# Fascia_physioBoardV0_1.net
KiCad netlist of a schematic drawn in EAGLE
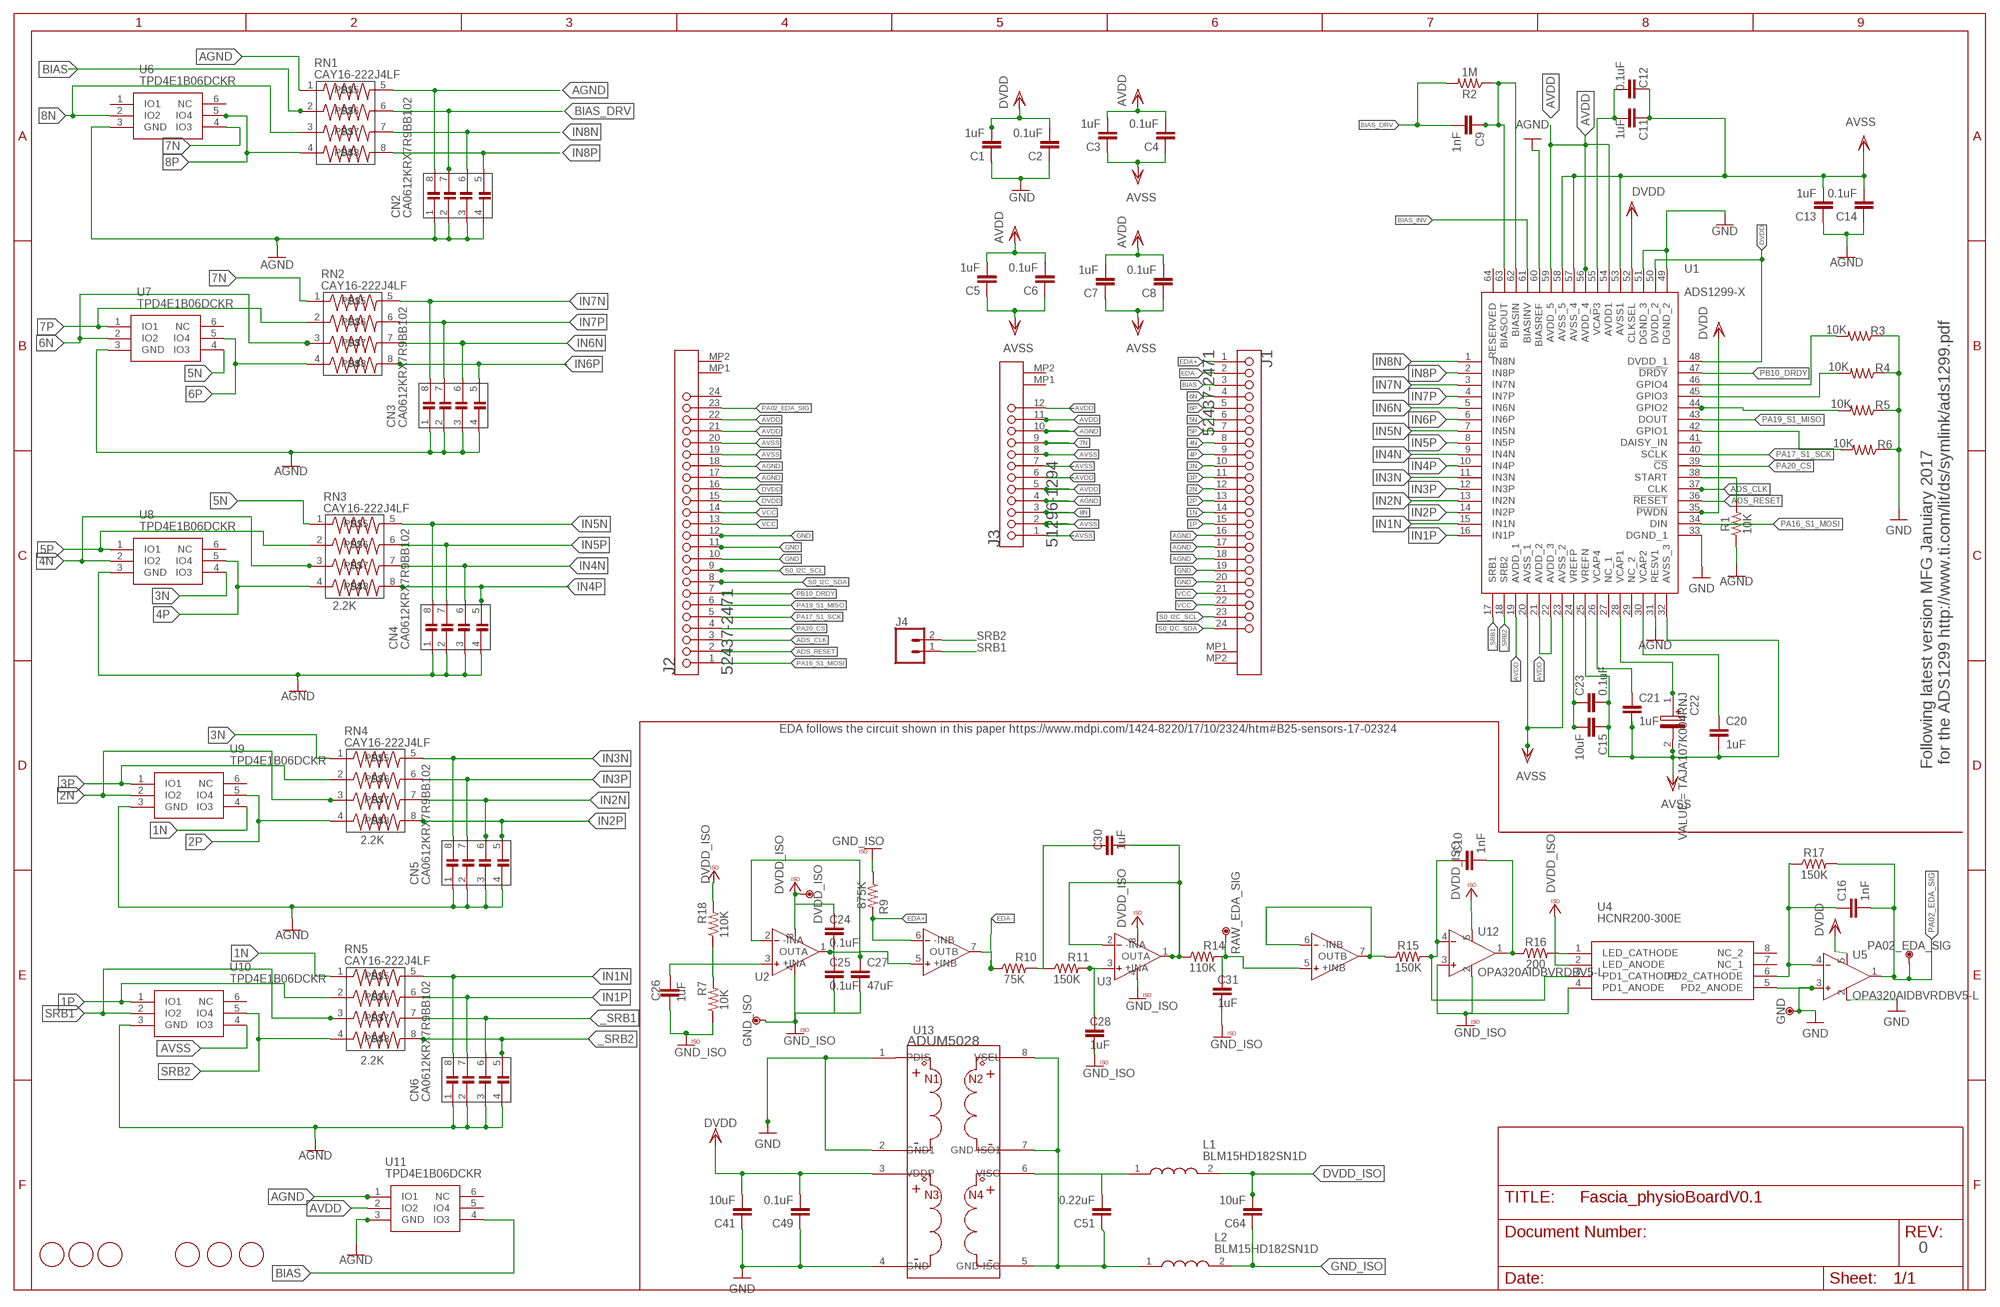
[diagram p0: schematic, sheet 1]

(export (version "E")
  (design (tool "Eeschema 10.0.6"))
  (components
    (comp (ref "C1")
      (value "1uF")
      (footprint "eagle-import:0402-TIGHT")
      (libsource (lib "eagle-import") (part "1UF-0402T-16V-10%"))
    )
    (comp (ref "C2")
      (value "0.1uF")
      (footprint "eagle-import:0402-TIGHT")
      (libsource (lib "eagle-import") (part "0.1UF-0402T-16V-10%"))
    )
    (comp (ref "C3")
      (value "1uF")
      (footprint "eagle-import:0402-TIGHT")
      (libsource (lib "eagle-import") (part "1UF-0402T-16V-10%"))
    )
    (comp (ref "C4")
      (value "0.1uF")
      (footprint "eagle-import:0402-TIGHT")
      (libsource (lib "eagle-import") (part "0.1UF-0402T-16V-10%"))
    )
    (comp (ref "C5")
      (value "1uF")
      (footprint "eagle-import:0402-TIGHT")
      (libsource (lib "eagle-import") (part "1UF-0402T-16V-10%"))
    )
    (comp (ref "C6")
      (value "0.1uF")
      (footprint "eagle-import:0402-TIGHT")
      (libsource (lib "eagle-import") (part "0.1UF-0402T-16V-10%"))
    )
    (comp (ref "C7")
      (value "1uF")
      (footprint "eagle-import:0402-TIGHT")
      (libsource (lib "eagle-import") (part "1UF-0402T-16V-10%"))
    )
    (comp (ref "C8")
      (value "0.1uF")
      (footprint "eagle-import:0402-TIGHT")
      (libsource (lib "eagle-import") (part "0.1UF-0402T-16V-10%"))
    )
    (comp (ref "C9")
      (value "1nF")
      (footprint "eagle-import:0402-TIGHT")
      (libsource (lib "eagle-import") (part "1NF-0402T-16V-10%"))
    )
    (comp (ref "C10")
      (value "1nF")
      (footprint "eagle-import:0402-TIGHT")
      (libsource (lib "eagle-import") (part "1NF-0402T-16V-10%"))
    )
    (comp (ref "C11")
      (value "1uF")
      (footprint "eagle-import:0402-TIGHT")
      (libsource (lib "eagle-import") (part "1UF-0402T-16V-10%"))
    )
    (comp (ref "C12")
      (value "0.1uF")
      (footprint "eagle-import:0402-TIGHT")
      (libsource (lib "eagle-import") (part "0.1UF-0402T-16V-10%"))
    )
    (comp (ref "C13")
      (value "1uF")
      (footprint "eagle-import:0402-TIGHT")
      (libsource (lib "eagle-import") (part "1UF-0402T-16V-10%"))
    )
    (comp (ref "C14")
      (value "0.1uF")
      (footprint "eagle-import:0402-TIGHT")
      (libsource (lib "eagle-import") (part "0.1UF-0402T-16V-10%"))
    )
    (comp (ref "C15")
      (value "10uF")
      (footprint "eagle-import:0402")
      (libsource (lib "eagle-import") (part "0.1UF-0402-16V-10%"))
    )
    (comp (ref "C16")
      (value "1nF")
      (footprint "eagle-import:0402-TIGHT")
      (libsource (lib "eagle-import") (part "1NF-0402T-16V-10%"))
    )
    (comp (ref "C20")
      (value "1uF")
      (footprint "eagle-import:0402-TIGHT")
      (libsource (lib "eagle-import") (part "1UF-0402T-16V-10%"))
    )
    (comp (ref "C21")
      (value "1uF")
      (footprint "eagle-import:0402-TIGHT")
      (libsource (lib "eagle-import") (part "1UF-0402T-16V-10%"))
    )
    (comp (ref "C22")
      (value "TAJA107K004RNJ")
      (footprint "eagle-import:CAPPM3216X180N")
      (fields
        (field (name "MOUSER_PART_NUMBER") "581-TAJA107K004RNJ")
        (field (name "RS_PART_NUMBER") "1360130")
      )
      (libsource (lib "eagle-import") (part "TAJA107K004RNJ"))
    )
    (comp (ref "C23")
      (value "0.1uF")
      (footprint "eagle-import:0402-TIGHT")
      (libsource (lib "eagle-import") (part "0.1UF-0402T-16V-10%"))
    )
    (comp (ref "C24")
      (value "0.1uF")
      (footprint "eagle-import:0402-TIGHT")
      (libsource (lib "eagle-import") (part "0.1UF-0402T-16V-10%"))
    )
    (comp (ref "C25")
      (value "0.1uF")
      (footprint "eagle-import:0402-TIGHT")
      (libsource (lib "eagle-import") (part "0.1UF-0402T-16V-10%"))
    )
    (comp (ref "C26")
      (value "1uF")
      (footprint "eagle-import:0402-TIGHT")
      (libsource (lib "eagle-import") (part "1UF-0402T-16V-10%"))
    )
    (comp (ref "C27")
      (value "47uF")
      (footprint "eagle-import:0603")
      (libsource (lib "eagle-import") (part "47UF-0603-25V-5%"))
    )
    (comp (ref "C28")
      (value "1uF")
      (footprint "eagle-import:0402-TIGHT")
      (libsource (lib "eagle-import") (part "1UF-0402T-16V-10%"))
    )
    (comp (ref "C30")
      (value "1uF")
      (footprint "eagle-import:0402-TIGHT")
      (libsource (lib "eagle-import") (part "1UF-0402T-16V-10%"))
    )
    (comp (ref "C31")
      (value "1uF")
      (footprint "eagle-import:0402-TIGHT")
      (libsource (lib "eagle-import") (part "1UF-0402T-16V-10%"))
    )
    (comp (ref "C41")
      (value "10uF")
      (footprint "eagle-import:0603")
      (libsource (lib "eagle-import") (part "10UF-0603-6.3V-20%"))
    )
    (comp (ref "C49")
      (value "0.1uF")
      (footprint "eagle-import:0402-TIGHT")
      (libsource (lib "eagle-import") (part "0.1UF-0402T-16V-10%"))
    )
    (comp (ref "C51")
      (value "0.22uF")
      (footprint "eagle-import:0402-TIGHT")
      (libsource (lib "eagle-import") (part "0.22UF-0402T-16V-10%"))
    )
    (comp (ref "C64")
      (value "10uF")
      (footprint "eagle-import:0603")
      (libsource (lib "eagle-import") (part "10UF-0603-6.3V-20%"))
    )
    (comp (ref "CN2")
      (value "CA0612KRX7R9BB102")
      (footprint "eagle-import:CA0612KRX7R9BB102")
      (fields
        (field (name "MOUSER_PART_NUMBER") "603-CA612KRX7R9BB102")
        (field (name "RS_PART_NUMBER") "6169789")
      )
      (libsource (lib "eagle-import") (part "CA0612KRX7R9BB102"))
    )
    (comp (ref "CN3")
      (value "CA0612KRX7R9BB102")
      (footprint "eagle-import:CA0612KRX7R9BB102")
      (fields
        (field (name "MOUSER_PART_NUMBER") "603-CA612KRX7R9BB102")
        (field (name "RS_PART_NUMBER") "6169789")
      )
      (libsource (lib "eagle-import") (part "CA0612KRX7R9BB102"))
    )
    (comp (ref "CN4")
      (value "CA0612KRX7R9BB102")
      (footprint "eagle-import:CA0612KRX7R9BB102")
      (fields
        (field (name "MOUSER_PART_NUMBER") "603-CA612KRX7R9BB102")
        (field (name "RS_PART_NUMBER") "6169789")
      )
      (libsource (lib "eagle-import") (part "CA0612KRX7R9BB102"))
    )
    (comp (ref "CN5")
      (value "CA0612KRX7R9BB102")
      (footprint "eagle-import:CA0612KRX7R9BB102")
      (fields
        (field (name "MOUSER_PART_NUMBER") "603-CA612KRX7R9BB102")
        (field (name "RS_PART_NUMBER") "6169789")
      )
      (libsource (lib "eagle-import") (part "CA0612KRX7R9BB102"))
    )
    (comp (ref "CN6")
      (value "CA0612KRX7R9BB102")
      (footprint "eagle-import:CA0612KRX7R9BB102")
      (fields
        (field (name "MOUSER_PART_NUMBER") "603-CA612KRX7R9BB102")
        (field (name "RS_PART_NUMBER") "6169789")
      )
      (libsource (lib "eagle-import") (part "CA0612KRX7R9BB102"))
    )
    (comp (ref "DVDD_ISO")
      (value "DNP")
      (footprint "eagle-import:TP-0.8MM")
      (libsource (lib "eagle-import") (part "TPTP-0.8MM"))
    )
    (comp (ref "FD1")
      (value "DNP")
      (footprint "eagle-import:FD-1-1.5")
      (libsource (lib "eagle-import") (part "FIDUCIAL-1.5MM"))
    )
    (comp (ref "FD2")
      (value "DNP")
      (footprint "eagle-import:FD-1-1.5")
      (libsource (lib "eagle-import") (part "FIDUCIAL-1.5MM"))
    )
    (comp (ref "FD3")
      (value "DNP")
      (footprint "eagle-import:FD-1-1.5")
      (libsource (lib "eagle-import") (part "FIDUCIAL-1.5MM"))
    )
    (comp (ref "FD4")
      (value "DNP")
      (footprint "eagle-import:FD-1-1.5")
      (libsource (lib "eagle-import") (part "FIDUCIAL-1.5MM"))
    )
    (comp (ref "FD5")
      (value "DNP")
      (footprint "eagle-import:FD-1-1.5")
      (libsource (lib "eagle-import") (part "FIDUCIAL-1.5MM"))
    )
    (comp (ref "FD6")
      (value "DNP")
      (footprint "eagle-import:FD-1-1.5")
      (libsource (lib "eagle-import") (part "FIDUCIAL-1.5MM"))
    )
    (comp (ref "GND")
      (value "DNP")
      (footprint "eagle-import:TP-0.8MM")
      (libsource (lib "eagle-import") (part "TPTP-0.8MM"))
    )
    (comp (ref "GND_ISO")
      (value "DNP")
      (footprint "eagle-import:TP-0.8MM")
      (libsource (lib "eagle-import") (part "TPTP-0.8MM"))
    )
    (comp (ref "J1")
      (value "MOLEX_52437-2471MOLEX_52437-2471_0_0")
      (footprint "eagle-import:MOLEX_52437-2471_0")
      (fields (field (name "MF") "Molex") (field (name "MPN") "52437-2471"))
      (libsource (lib "eagle-import") (part "MOLEX_52437-2471MOLEX_52437-2471_0_0"))
    )
    (comp (ref "J2")
      (value "MOLEX_52437-2471MOLEX_52437-2471_0_0")
      (footprint "eagle-import:MOLEX_52437-2471_0")
      (fields (field (name "MF") "Molex") (field (name "MPN") "52437-2471"))
      (libsource (lib "eagle-import") (part "MOLEX_52437-2471MOLEX_52437-2471_0_0"))
    )
    (comp (ref "J3")
      (value "MOLEX_51296-1294MOLEX_51296-1294_0_0")
      (footprint "eagle-import:MOLEX_51296-1294_0")
      (fields (field (name "MF") "Molex") (field (name "MPN") "51296-1294"))
      (libsource (lib "eagle-import") (part "MOLEX_51296-1294MOLEX_51296-1294_0_0"))
    )
    (comp (ref "J4")
      (value "CONN_02")
      (footprint "eagle-import:1X02")
      (libsource (lib "eagle-import") (part "CONN_02"))
    )
    (comp (ref "L1")
      (value "BLM15HD182SN1D")
      (footprint "eagle-import:INDC1005X55N")
      (fields
        (field (name "MOUSER_PART_NUMBER") "81-BLM15HD182SN1D")
        (field (name "RS_PART_NUMBER") "7926224P")
      )
      (libsource (lib "eagle-import") (part "BLM15HD182SN1D"))
    )
    (comp (ref "L2")
      (value "BLM15HD182SN1D")
      (footprint "eagle-import:INDC1005X55N")
      (fields
        (field (name "MOUSER_PART_NUMBER") "81-BLM15HD182SN1D")
        (field (name "RS_PART_NUMBER") "7926224P")
      )
      (libsource (lib "eagle-import") (part "BLM15HD182SN1D"))
    )
    (comp (ref "PA02_EDA_SIG")
      (value "DNP")
      (footprint "eagle-import:TP-0.8MM")
      (libsource (lib "eagle-import") (part "TPTP-0.8MM"))
    )
    (comp (ref "R1")
      (value "10K")
      (footprint "eagle-import:0402-TIGHT")
      (libsource (lib "eagle-import") (part "10K"))
    )
    (comp (ref "R2")
      (value "1M")
      (footprint "eagle-import:0402-TIGHT")
      (libsource (lib "eagle-import") (part "1M"))
    )
    (comp (ref "R3")
      (value "10K")
      (footprint "eagle-import:0402-TIGHT")
      (libsource (lib "eagle-import") (part "10K"))
    )
    (comp (ref "R4")
      (value "10K")
      (footprint "eagle-import:0402-TIGHT")
      (libsource (lib "eagle-import") (part "10K"))
    )
    (comp (ref "R5")
      (value "10K")
      (footprint "eagle-import:0402-TIGHT")
      (libsource (lib "eagle-import") (part "10K"))
    )
    (comp (ref "R6")
      (value "10K")
      (footprint "eagle-import:0402-TIGHT")
      (libsource (lib "eagle-import") (part "10K"))
    )
    (comp (ref "R7")
      (value "10K")
      (footprint "eagle-import:0402-TIGHT")
      (libsource (lib "eagle-import") (part "10K"))
    )
    (comp (ref "R9")
      (value "875K")
      (footprint "eagle-import:0402-TIGHT")
      (libsource (lib "eagle-import") (part "875K"))
    )
    (comp (ref "R10")
      (value "75K")
      (footprint "eagle-import:0402-TIGHT")
      (libsource (lib "eagle-import") (part "75K"))
    )
    (comp (ref "R11")
      (value "150K")
      (footprint "eagle-import:0402-TIGHT")
      (libsource (lib "eagle-import") (part "150K"))
    )
    (comp (ref "R14")
      (value "110K")
      (footprint "eagle-import:0402-TIGHT")
      (libsource (lib "eagle-import") (part "110K"))
    )
    (comp (ref "R15")
      (value "150K")
      (footprint "eagle-import:0402-TIGHT")
      (libsource (lib "eagle-import") (part "150K"))
    )
    (comp (ref "R16")
      (value "200")
      (footprint "eagle-import:0402-TIGHT")
      (libsource (lib "eagle-import") (part "200"))
    )
    (comp (ref "R17")
      (value "150K")
      (footprint "eagle-import:0402-TIGHT")
      (libsource (lib "eagle-import") (part "150K"))
    )
    (comp (ref "R18")
      (value "110K")
      (footprint "eagle-import:0402-TIGHT")
      (libsource (lib "eagle-import") (part "110K"))
    )
    (comp (ref "RAW_EDA_SIG")
      (value "DNP")
      (footprint "eagle-import:TP-0.8MM")
      (libsource (lib "eagle-import") (part "TPTP-0.8MM"))
    )
    (comp (ref "RN1")
      (value "CAY16-222J4LF")
      (footprint "eagle-import:CAY16-222J4LF")
      (fields (field (name "MANUFACTURER_PART_NUMBER") "CAY16-222J4LF  "))
      (libsource (lib "eagle-import") (part "CAY16-222J4LF"))
    )
    (comp (ref "RN2")
      (value "CAY16-222J4LF")
      (footprint "eagle-import:CAY16-222J4LF")
      (fields (field (name "MANUFACTURER_PART_NUMBER") "CAY16-222J4LF  "))
      (libsource (lib "eagle-import") (part "CAY16-222J4LF"))
    )
    (comp (ref "RN3")
      (value "CAY16-222J4LF")
      (footprint "eagle-import:CAY16-222J4LF")
      (fields (field (name "MANUFACTURER_PART_NUMBER") "CAY16-222J4LF  "))
      (libsource (lib "eagle-import") (part "CAY16-222J4LF"))
    )
    (comp (ref "RN4")
      (value "CAY16-222J4LF")
      (footprint "eagle-import:CAY16-222J4LF")
      (fields (field (name "MANUFACTURER_PART_NUMBER") "CAY16-222J4LF  "))
      (libsource (lib "eagle-import") (part "CAY16-222J4LF"))
    )
    (comp (ref "RN5")
      (value "CAY16-222J4LF")
      (footprint "eagle-import:CAY16-222J4LF")
      (fields (field (name "MANUFACTURER_PART_NUMBER") "CAY16-222J4LF  "))
      (libsource (lib "eagle-import") (part "CAY16-222J4LF"))
    )
    (comp (ref "U1")
      (value "ADS1299-X")
      (footprint "eagle-import:QFP50P1200X1200X120-64N")
      (libsource (lib "eagle-import") (part "ADS1299-X"))
    )
    (comp (ref "U2")
      (value "OPA2320AIDGKT_NOVA8-SOIC-L")
      (footprint "eagle-import:D8-L")
      (libsource (lib "eagle-import") (part "OPA2320AIDGKT_NOVA8-SOIC-L"))
    )
    (comp (ref "U3")
      (value "OPA2320AIDGKT_NOVAL8-SOIC-L")
      (footprint "eagle-import:D8-L")
      (libsource (lib "eagle-import") (part "OPA2320AIDGKT_NOVAL8-SOIC-L"))
    )
    (comp (ref "U4")
      (value "HCNR200-300E")
      (footprint "eagle-import:SOP254P1230X400-8N")
      (fields
        (field (name "MOUSER_PART_NUMBER") "630-HCNR200-300E")
        (field (name "RS_PART_NUMBER") "6935264P")
      )
      (libsource (lib "eagle-import") (part "HCNR200-300E"))
    )
    (comp (ref "U5")
      (value "OPA320AIDBVRDBV5-L")
      (footprint "eagle-import:DBV5-L")
      (fields (field (name "MANUFACTURER_PART_NUMBER") "OPA320AIDBVR"))
      (libsource (lib "eagle-import") (part "OPA320AIDBVRDBV5-L"))
    )
    (comp (ref "U6")
      (value "TPD4E1B06DCKR")
      (footprint "eagle-import:SOT65P210X110-6N")
      (fields
        (field (name "MOUSER_PART_NUMBER") "595-TPD4E1B06DCKR")
        (field (name "RS_PART_NUMBER") "8255330P")
      )
      (libsource (lib "eagle-import") (part "TPD4E1B06DCKR"))
    )
    (comp (ref "U7")
      (value "TPD4E1B06DCKR")
      (footprint "eagle-import:SOT65P210X110-6N")
      (fields
        (field (name "MOUSER_PART_NUMBER") "595-TPD4E1B06DCKR")
        (field (name "RS_PART_NUMBER") "8255330P")
      )
      (libsource (lib "eagle-import") (part "TPD4E1B06DCKR"))
    )
    (comp (ref "U8")
      (value "TPD4E1B06DCKR")
      (footprint "eagle-import:SOT65P210X110-6N")
      (fields
        (field (name "MOUSER_PART_NUMBER") "595-TPD4E1B06DCKR")
        (field (name "RS_PART_NUMBER") "8255330P")
      )
      (libsource (lib "eagle-import") (part "TPD4E1B06DCKR"))
    )
    (comp (ref "U9")
      (value "TPD4E1B06DCKR")
      (footprint "eagle-import:SOT65P210X110-6N")
      (fields
        (field (name "MOUSER_PART_NUMBER") "595-TPD4E1B06DCKR")
        (field (name "RS_PART_NUMBER") "8255330P")
      )
      (libsource (lib "eagle-import") (part "TPD4E1B06DCKR"))
    )
    (comp (ref "U10")
      (value "TPD4E1B06DCKR")
      (footprint "eagle-import:SOT65P210X110-6N")
      (fields
        (field (name "MOUSER_PART_NUMBER") "595-TPD4E1B06DCKR")
        (field (name "RS_PART_NUMBER") "8255330P")
      )
      (libsource (lib "eagle-import") (part "TPD4E1B06DCKR"))
    )
    (comp (ref "U11")
      (value "TPD4E1B06DCKR")
      (footprint "eagle-import:SOT65P210X110-6N")
      (fields
        (field (name "MOUSER_PART_NUMBER") "595-TPD4E1B06DCKR")
        (field (name "RS_PART_NUMBER") "8255330P")
      )
      (libsource (lib "eagle-import") (part "TPD4E1B06DCKR"))
    )
    (comp (ref "U12")
      (value "OPA320AIDBVRDBV5-L")
      (footprint "eagle-import:DBV5-L")
      (fields (field (name "MANUFACTURER_PART_NUMBER") "OPA320AIDBVR"))
      (libsource (lib "eagle-import") (part "OPA320AIDBVRDBV5-L"))
    )
    (comp (ref "U13")
      (value "ADUM5028")
      (footprint "eagle-import:SOIC_IC")
      (libsource (lib "eagle-import") (part "ADUM5028"))
    )
  )
  (nets
    (net (code "1") (name "/N$12") (class "Default")
      (node (ref "C26") (pin "1") (pinfunction "1_1") (pintype "passive"))
      (node (ref "R18") (pin "1") (pinfunction "1_1") (pintype "passive"))
      (node (ref "R7") (pin "2") (pinfunction "2_2") (pintype "passive"))
      (node (ref "U2") (pin "3") (pinfunction "+INA_3") (pintype "input"))
    )
    (net (code "2") (name "1N") (class "Default")
      (node (ref "J1") (pin "14") (pinfunction "14_14") (pintype "passive"))
      (node (ref "RN5") (pin "1") (pinfunction "P$1_1") (pintype "bidirectional"))
      (node (ref "U9") (pin "4") (pinfunction "IO3_4") (pintype "bidirectional"))
    )
    (net (code "3") (name "1P") (class "Default")
      (node (ref "J1") (pin "15") (pinfunction "15_15") (pintype "passive"))
      (node (ref "RN5") (pin "2") (pinfunction "P$2_2") (pintype "bidirectional"))
      (node (ref "U10") (pin "1") (pinfunction "IO1_1") (pintype "bidirectional"))
    )
    (net (code "4") (name "2N") (class "Default")
      (node (ref "J1") (pin "12") (pinfunction "12_12") (pintype "passive"))
      (node (ref "RN4") (pin "3") (pinfunction "P$3_3") (pintype "bidirectional"))
      (node (ref "U9") (pin "2") (pinfunction "IO2_2") (pintype "bidirectional"))
    )
    (net (code "5") (name "2P") (class "Default")
      (node (ref "J1") (pin "13") (pinfunction "13_13") (pintype "passive"))
      (node (ref "RN4") (pin "4") (pinfunction "P$4_4") (pintype "bidirectional"))
      (node (ref "U9") (pin "5") (pinfunction "IO4_5") (pintype "bidirectional"))
    )
    (net (code "6") (name "3N") (class "Default")
      (node (ref "J1") (pin "10") (pinfunction "10_10") (pintype "passive"))
      (node (ref "RN4") (pin "1") (pinfunction "P$1_1") (pintype "bidirectional"))
      (node (ref "U8") (pin "4") (pinfunction "IO3_4") (pintype "bidirectional"))
    )
    (net (code "7") (name "3P") (class "Default")
      (node (ref "J1") (pin "11") (pinfunction "11_11") (pintype "passive"))
      (node (ref "RN4") (pin "2") (pinfunction "P$2_2") (pintype "bidirectional"))
      (node (ref "U9") (pin "1") (pinfunction "IO1_1") (pintype "bidirectional"))
    )
    (net (code "8") (name "4N") (class "Default")
      (node (ref "J1") (pin "8") (pinfunction "8_8") (pintype "passive"))
      (node (ref "RN3") (pin "3") (pinfunction "P$3_3") (pintype "bidirectional"))
      (node (ref "U8") (pin "2") (pinfunction "IO2_2") (pintype "bidirectional"))
    )
    (net (code "9") (name "4P") (class "Default")
      (node (ref "J1") (pin "9") (pinfunction "9_9") (pintype "passive"))
      (node (ref "RN3") (pin "4") (pinfunction "P$4_4") (pintype "bidirectional"))
      (node (ref "U8") (pin "5") (pinfunction "IO4_5") (pintype "bidirectional"))
    )
    (net (code "10") (name "5N") (class "Default")
      (node (ref "J1") (pin "6") (pinfunction "6_6") (pintype "passive"))
      (node (ref "RN3") (pin "1") (pinfunction "P$1_1") (pintype "bidirectional"))
      (node (ref "U7") (pin "4") (pinfunction "IO3_4") (pintype "bidirectional"))
    )
    (net (code "11") (name "5P") (class "Default")
      (node (ref "J1") (pin "7") (pinfunction "7_7") (pintype "passive"))
      (node (ref "RN3") (pin "2") (pinfunction "P$2_2") (pintype "bidirectional"))
      (node (ref "U8") (pin "1") (pinfunction "IO1_1") (pintype "bidirectional"))
    )
    (net (code "12") (name "6N") (class "Default")
      (node (ref "J1") (pin "4") (pinfunction "4_4") (pintype "passive"))
      (node (ref "RN2") (pin "3") (pinfunction "P$3_3") (pintype "bidirectional"))
      (node (ref "U7") (pin "2") (pinfunction "IO2_2") (pintype "bidirectional"))
    )
    (net (code "13") (name "6P") (class "Default")
      (node (ref "J1") (pin "5") (pinfunction "5_5") (pintype "passive"))
      (node (ref "RN2") (pin "4") (pinfunction "P$4_4") (pintype "bidirectional"))
      (node (ref "U7") (pin "5") (pinfunction "IO4_5") (pintype "bidirectional"))
    )
    (net (code "14") (name "7N") (class "Default")
      (node (ref "J3") (pin "9") (pinfunction "9_9") (pintype "passive"))
      (node (ref "RN2") (pin "1") (pinfunction "P$1_1") (pintype "bidirectional"))
      (node (ref "U6") (pin "4") (pinfunction "IO3_4") (pintype "bidirectional"))
    )
    (net (code "15") (name "7P") (class "Default")
      (node (ref "RN2") (pin "2") (pinfunction "P$2_2") (pintype "bidirectional"))
      (node (ref "U7") (pin "1") (pinfunction "IO1_1") (pintype "bidirectional"))
    )
    (net (code "16") (name "8N") (class "Default")
      (node (ref "J3") (pin "3") (pinfunction "3_3") (pintype "passive"))
      (node (ref "RN1") (pin "3") (pinfunction "P$3_3") (pintype "bidirectional"))
      (node (ref "U6") (pin "2") (pinfunction "IO2_2") (pintype "bidirectional"))
    )
    (net (code "17") (name "8P") (class "Default")
      (node (ref "RN1") (pin "4") (pinfunction "P$4_4") (pintype "bidirectional"))
      (node (ref "U6") (pin "5") (pinfunction "IO4_5") (pintype "bidirectional"))
    )
    (net (code "18") (name "ADS_CLK") (class "Default")
      (node (ref "J2") (pin "3") (pinfunction "3_3") (pintype "passive"))
      (node (ref "U1") (pin "37") (pinfunction "CLK_37") (pintype "bidirectional"))
    )
    (net (code "19") (name "ADS_RESET") (class "Default")
      (node (ref "J2") (pin "2") (pinfunction "2_2") (pintype "passive"))
      (node (ref "U1") (pin "36") (pinfunction "~{RESET}_36") (pintype "bidirectional"))
    )
    (net (code "20") (name "AGND") (class "Default")
      (node (ref "C13") (pin "1") (pinfunction "1_1") (pintype "passive"))
      (node (ref "C14") (pin "1") (pinfunction "1_1") (pintype "passive"))
      (node (ref "CN2") (pin "1") (pinfunction "C10_1") (pintype "bidirectional"))
      (node (ref "CN2") (pin "2") (pinfunction "C11_2") (pintype "bidirectional"))
      (node (ref "CN2") (pin "3") (pinfunction "C12_3") (pintype "bidirectional"))
      (node (ref "CN2") (pin "4") (pinfunction "C13_4") (pintype "bidirectional"))
      (node (ref "CN2") (pin "8") (pinfunction "C17_8") (pintype "bidirectional"))
      (node (ref "CN3") (pin "1") (pinfunction "C10_1") (pintype "bidirectional"))
      (node (ref "CN3") (pin "2") (pinfunction "C11_2") (pintype "bidirectional"))
      (node (ref "CN3") (pin "3") (pinfunction "C12_3") (pintype "bidirectional"))
      (node (ref "CN3") (pin "4") (pinfunction "C13_4") (pintype "bidirectional"))
      (node (ref "CN4") (pin "1") (pinfunction "C10_1") (pintype "bidirectional"))
      (node (ref "CN4") (pin "2") (pinfunction "C11_2") (pintype "bidirectional"))
      (node (ref "CN4") (pin "3") (pinfunction "C12_3") (pintype "bidirectional"))
      (node (ref "CN4") (pin "4") (pinfunction "C13_4") (pintype "bidirectional"))
      (node (ref "CN5") (pin "1") (pinfunction "C10_1") (pintype "bidirectional"))
      (node (ref "CN5") (pin "2") (pinfunction "C11_2") (pintype "bidirectional"))
      (node (ref "CN5") (pin "3") (pinfunction "C12_3") (pintype "bidirectional"))
      (node (ref "CN5") (pin "4") (pinfunction "C13_4") (pintype "bidirectional"))
      (node (ref "CN6") (pin "1") (pinfunction "C10_1") (pintype "bidirectional"))
      (node (ref "CN6") (pin "2") (pinfunction "C11_2") (pintype "bidirectional"))
      (node (ref "CN6") (pin "3") (pinfunction "C12_3") (pintype "bidirectional"))
      (node (ref "CN6") (pin "4") (pinfunction "C13_4") (pintype "bidirectional"))
      (node (ref "J1") (pin "16") (pinfunction "16_16") (pintype "passive"))
      (node (ref "J1") (pin "17") (pinfunction "17_17") (pintype "passive"))
      (node (ref "J1") (pin "18") (pinfunction "18_18") (pintype "passive"))
      (node (ref "J2") (pin "17") (pinfunction "17_17") (pintype "passive"))
      (node (ref "J2") (pin "18") (pinfunction "18_18") (pintype "passive"))
      (node (ref "J3") (pin "10") (pinfunction "10_10") (pintype "passive"))
      (node (ref "J3") (pin "4") (pinfunction "4_4") (pintype "passive"))
      (node (ref "R1") (pin "1") (pinfunction "1_1") (pintype "passive"))
      (node (ref "RN1") (pin "1") (pinfunction "P$1_1") (pintype "bidirectional"))
      (node (ref "RN1") (pin "5") (pinfunction "P$5_5") (pintype "bidirectional"))
      (node (ref "U1") (pin "31") (pinfunction "RESV1_31") (pintype "bidirectional"))
      (node (ref "U1") (pin "60") (pinfunction "BIASREF_60") (pintype "bidirectional"))
      (node (ref "U10") (pin "3") (pinfunction "GND_3") (pintype "power_in"))
      (node (ref "U11") (pin "1") (pinfunction "IO1_1") (pintype "bidirectional"))
      (node (ref "U11") (pin "3") (pinfunction "GND_3") (pintype "power_in"))
      (node (ref "U6") (pin "3") (pinfunction "GND_3") (pintype "power_in"))
      (node (ref "U7") (pin "3") (pinfunction "GND_3") (pintype "power_in"))
      (node (ref "U8") (pin "3") (pinfunction "GND_3") (pintype "power_in"))
      (node (ref "U9") (pin "3") (pinfunction "GND_3") (pintype "power_in"))
    )
    (net (code "21") (name "AVDD") (class "Default")
      (node (ref "C3") (pin "2") (pinfunction "2_2") (pintype "passive"))
      (node (ref "C4") (pin "2") (pinfunction "2_2") (pintype "passive"))
      (node (ref "C5") (pin "2") (pinfunction "2_2") (pintype "passive"))
      (node (ref "C6") (pin "2") (pinfunction "2_2") (pintype "passive"))
      (node (ref "C7") (pin "2") (pinfunction "2_2") (pintype "passive"))
      (node (ref "C8") (pin "2") (pinfunction "2_2") (pintype "passive"))
      (node (ref "J2") (pin "21") (pinfunction "21_21") (pintype "passive"))
      (node (ref "J2") (pin "22") (pinfunction "22_22") (pintype "passive"))
      (node (ref "J3") (pin "11") (pinfunction "11_11") (pintype "passive"))
      (node (ref "J3") (pin "12") (pinfunction "12_12") (pintype "passive"))
      (node (ref "J3") (pin "5") (pinfunction "5_5") (pintype "passive"))
      (node (ref "J3") (pin "6") (pinfunction "6_6") (pintype "passive"))
      (node (ref "U1") (pin "19") (pinfunction "AVDD_1_19") (pintype "bidirectional"))
      (node (ref "U1") (pin "21") (pinfunction "AVDD_2_21") (pintype "bidirectional"))
      (node (ref "U1") (pin "22") (pinfunction "AVDD_3_22") (pintype "bidirectional"))
      (node (ref "U1") (pin "54") (pinfunction "AVDD1_54") (pintype "bidirectional"))
      (node (ref "U1") (pin "56") (pinfunction "AVDD_4_56") (pintype "bidirectional"))
      (node (ref "U1") (pin "59") (pinfunction "AVDD_5_59") (pintype "bidirectional"))
      (node (ref "U11") (pin "2") (pinfunction "IO2_2") (pintype "bidirectional"))
    )
    (net (code "22") (name "AVSS") (class "Default")
      (node (ref "C11") (pin "1") (pinfunction "1_1") (pintype "passive"))
      (node (ref "C12") (pin "1") (pinfunction "1_1") (pintype "passive"))
      (node (ref "C13") (pin "2") (pinfunction "2_2") (pintype "passive"))
      (node (ref "C14") (pin "2") (pinfunction "2_2") (pintype "passive"))
      (node (ref "C15") (pin "1") (pinfunction "1_1") (pintype "passive"))
      (node (ref "C20") (pin "2") (pinfunction "2_2") (pintype "passive"))
      (node (ref "C21") (pin "2") (pinfunction "2_2") (pintype "passive"))
      (node (ref "C22") (pin "2") (pinfunction "-_2") (pintype "bidirectional"))
      (node (ref "C23") (pin "2") (pinfunction "2_2") (pintype "passive"))
      (node (ref "C3") (pin "1") (pinfunction "1_1") (pintype "passive"))
      (node (ref "C4") (pin "1") (pinfunction "1_1") (pintype "passive"))
      (node (ref "C5") (pin "1") (pinfunction "1_1") (pintype "passive"))
      (node (ref "C6") (pin "1") (pinfunction "1_1") (pintype "passive"))
      (node (ref "C7") (pin "1") (pinfunction "1_1") (pintype "passive"))
      (node (ref "C8") (pin "1") (pinfunction "1_1") (pintype "passive"))
      (node (ref "J2") (pin "19") (pinfunction "19_19") (pintype "passive"))
      (node (ref "J2") (pin "20") (pinfunction "20_20") (pintype "passive"))
      (node (ref "J3") (pin "1") (pinfunction "1_1") (pintype "passive"))
      (node (ref "J3") (pin "2") (pinfunction "2_2") (pintype "passive"))
      (node (ref "J3") (pin "7") (pinfunction "7_7") (pintype "passive"))
      (node (ref "J3") (pin "8") (pinfunction "8_8") (pintype "passive"))
      (node (ref "U1") (pin "20") (pinfunction "AVSS_1_20") (pintype "bidirectional"))
      (node (ref "U1") (pin "23") (pinfunction "AVSS_2_23") (pintype "bidirectional"))
      (node (ref "U1") (pin "25") (pinfunction "VREFN_25") (pintype "bidirectional"))
      (node (ref "U1") (pin "32") (pinfunction "AVSS_3_32") (pintype "bidirectional"))
      (node (ref "U1") (pin "53") (pinfunction "AVSS1_53") (pintype "bidirectional"))
      (node (ref "U1") (pin "57") (pinfunction "AVSS_4_57") (pintype "bidirectional"))
      (node (ref "U1") (pin "58") (pinfunction "AVSS_5_58") (pintype "bidirectional"))
      (node (ref "U10") (pin "4") (pinfunction "IO3_4") (pintype "bidirectional"))
    )
    (net (code "23") (name "BIAS") (class "Default")
      (node (ref "J1") (pin "3") (pinfunction "3_3") (pintype "passive"))
      (node (ref "RN1") (pin "2") (pinfunction "P$2_2") (pintype "bidirectional"))
      (node (ref "U11") (pin "4") (pinfunction "IO3_4") (pintype "bidirectional"))
    )
    (net (code "24") (name "BIAS_DRV") (class "Default")
      (node (ref "C9") (pin "2") (pinfunction "2_2") (pintype "passive"))
      (node (ref "CN2") (pin "7") (pinfunction "C16_7") (pintype "bidirectional"))
      (node (ref "R2") (pin "2") (pinfunction "2_2") (pintype "passive"))
      (node (ref "RN1") (pin "6") (pinfunction "P$6_6") (pintype "bidirectional"))
    )
    (net (code "25") (name "BIAS_INV") (class "Default")
      (node (ref "U1") (pin "61") (pinfunction "BIASINV_61") (pintype "bidirectional"))
    )
    (net (code "26") (name "DVDD") (class "Default")
      (node (ref "C1") (pin "2") (pinfunction "2_2") (pintype "passive"))
      (node (ref "C2") (pin "2") (pinfunction "2_2") (pintype "passive"))
      (node (ref "C41") (pin "2") (pinfunction "2_2") (pintype "passive"))
      (node (ref "C49") (pin "2") (pinfunction "2_2") (pintype "passive"))
      (node (ref "J2") (pin "15") (pinfunction "15_15") (pintype "passive"))
      (node (ref "J2") (pin "16") (pinfunction "16_16") (pintype "passive"))
      (node (ref "U1") (pin "35") (pinfunction "~{PWDN}_35") (pintype "bidirectional"))
      (node (ref "U1") (pin "48") (pinfunction "DVDD_1_48") (pintype "bidirectional"))
      (node (ref "U1") (pin "50") (pinfunction "DVDD_2_50") (pintype "bidirectional"))
      (node (ref "U1") (pin "52") (pinfunction "CLKSEL_52") (pintype "bidirectional"))
      (node (ref "U13") (pin "3") (pinfunction "VDDP_3") (pintype "bidirectional"))
      (node (ref "U5") (pin "5") (pinfunction "V+_5") (pintype "bidirectional"))
    )
    (net (code "27") (name "DVDD_ISO") (class "Default")
      (node (ref "C24") (pin "1") (pinfunction "1_1") (pintype "passive"))
      (node (ref "C64") (pin "2") (pinfunction "2_2") (pintype "passive"))
      (node (ref "DVDD_ISO") (pin "X") (pinfunction "P$1_X") (pintype "passive"))
      (node (ref "L1") (pin "2") (pinfunction "2_2") (pintype "bidirectional"))
      (node (ref "R18") (pin "2") (pinfunction "2_2") (pintype "passive"))
      (node (ref "U12") (pin "5") (pinfunction "V+_5") (pintype "bidirectional"))
      (node (ref "U2") (pin "8") (pinfunction "V+_8") (pintype "bidirectional"))
      (node (ref "U3") (pin "8") (pinfunction "V+_8") (pintype "bidirectional"))
      (node (ref "U4") (pin "2") (pinfunction "LED_ANODE_2") (pintype "bidirectional"))
    )
    (net (code "28") (name "EDA+") (class "Default")
      (node (ref "J1") (pin "1") (pinfunction "1_1") (pintype "passive"))
      (node (ref "R9") (pin "2") (pinfunction "2_2") (pintype "passive"))
      (node (ref "U2") (pin "6") (pinfunction "-INB_6") (pintype "input"))
    )
    (net (code "29") (name "EDA-") (class "Default")
      (node (ref "J1") (pin "2") (pinfunction "2_2") (pintype "passive"))
      (node (ref "R10") (pin "1") (pinfunction "1_1") (pintype "passive"))
      (node (ref "U2") (pin "7") (pinfunction "OUTB_7") (pintype "output"))
    )
    (net (code "30") (name "GND") (class "Default")
      (node (ref "C1") (pin "1") (pinfunction "1_1") (pintype "passive"))
      (node (ref "C2") (pin "1") (pinfunction "1_1") (pintype "passive"))
      (node (ref "C41") (pin "1") (pinfunction "1_1") (pintype "passive"))
      (node (ref "C49") (pin "1") (pinfunction "1_1") (pintype "passive"))
      (node (ref "GND") (pin "X") (pinfunction "P$1_X") (pintype "passive"))
      (node (ref "J1") (pin "19") (pinfunction "19_19") (pintype "passive"))
      (node (ref "J1") (pin "20") (pinfunction "20_20") (pintype "passive"))
      (node (ref "J2") (pin "10") (pinfunction "10_10") (pintype "passive"))
      (node (ref "J2") (pin "11") (pinfunction "11_11") (pintype "passive"))
      (node (ref "J2") (pin "12") (pinfunction "12_12") (pintype "passive"))
      (node (ref "R3") (pin "1") (pinfunction "1_1") (pintype "passive"))
      (node (ref "R4") (pin "1") (pinfunction "1_1") (pintype "passive"))
      (node (ref "R5") (pin "1") (pinfunction "1_1") (pintype "passive"))
      (node (ref "R6") (pin "1") (pinfunction "1_1") (pintype "passive"))
      (node (ref "U1") (pin "33") (pinfunction "DGND_1_33") (pintype "bidirectional"))
      (node (ref "U1") (pin "49") (pinfunction "DGND_2_49") (pintype "bidirectional"))
      (node (ref "U1") (pin "51") (pinfunction "DGND_3_51") (pintype "bidirectional"))
      (node (ref "U13") (pin "1") (pinfunction "PDIS_1") (pintype "bidirectional"))
      (node (ref "U13") (pin "2") (pinfunction "GND1_2") (pintype "bidirectional"))
      (node (ref "U13") (pin "4") (pinfunction "GND_4") (pintype "bidirectional"))
      (node (ref "U4") (pin "5") (pinfunction "PD2_ANODE_5") (pintype "bidirectional"))
      (node (ref "U5") (pin "2") (pinfunction "V-_2") (pintype "bidirectional"))
      (node (ref "U5") (pin "3") (pinfunction "IN+_3") (pintype "input"))
    )
    (net (code "31") (name "GND_ISO") (class "Default")
      (node (ref "C25") (pin "2") (pinfunction "2_2") (pintype "passive"))
      (node (ref "C26") (pin "2") (pinfunction "2_2") (pintype "passive"))
      (node (ref "C27") (pin "2") (pinfunction "2_2") (pintype "passive"))
      (node (ref "C28") (pin "2") (pinfunction "2_2") (pintype "passive"))
      (node (ref "C31") (pin "2") (pinfunction "2_2") (pintype "passive"))
      (node (ref "C51") (pin "1") (pinfunction "1_1") (pintype "passive"))
      (node (ref "C64") (pin "1") (pinfunction "1_1") (pintype "passive"))
      (node (ref "GND_ISO") (pin "X") (pinfunction "P$1_X") (pintype "passive"))
      (node (ref "L2") (pin "1") (pinfunction "1_1") (pintype "bidirectional"))
      (node (ref "L2") (pin "2") (pinfunction "2_2") (pintype "bidirectional"))
      (node (ref "R7") (pin "1") (pinfunction "1_1") (pintype "passive"))
      (node (ref "R9") (pin "1") (pinfunction "1_1") (pintype "passive"))
      (node (ref "U12") (pin "2") (pinfunction "V-_2") (pintype "bidirectional"))
      (node (ref "U12") (pin "3") (pinfunction "IN+_3") (pintype "input"))
      (node (ref "U13") (pin "5") (pinfunction "GND-ISO_5") (pintype "bidirectional"))
      (node (ref "U13") (pin "7") (pinfunction "GND-ISO1_7") (pintype "bidirectional"))
      (node (ref "U13") (pin "8") (pinfunction "VSEL_8") (pintype "bidirectional"))
      (node (ref "U2") (pin "4") (pinfunction "V-_4") (pintype "bidirectional"))
      (node (ref "U3") (pin "4") (pinfunction "V-_4") (pintype "bidirectional"))
      (node (ref "U4") (pin "4") (pinfunction "PD1_ANODE_4") (pintype "bidirectional"))
    )
    (net (code "32") (name "IN1N") (class "Default")
      (node (ref "CN6") (pin "8") (pinfunction "C17_8") (pintype "bidirectional"))
      (node (ref "RN5") (pin "5") (pinfunction "P$5_5") (pintype "bidirectional"))
      (node (ref "U1") (pin "15") (pinfunction "IN1N_15") (pintype "bidirectional"))
    )
    (net (code "33") (name "IN1P") (class "Default")
      (node (ref "CN6") (pin "7") (pinfunction "C16_7") (pintype "bidirectional"))
      (node (ref "RN5") (pin "6") (pinfunction "P$6_6") (pintype "bidirectional"))
      (node (ref "U1") (pin "16") (pinfunction "IN1P_16") (pintype "bidirectional"))
    )
    (net (code "34") (name "IN2N") (class "Default")
      (node (ref "CN5") (pin "6") (pinfunction "C15_6") (pintype "bidirectional"))
      (node (ref "RN4") (pin "7") (pinfunction "P$7_7") (pintype "bidirectional"))
      (node (ref "U1") (pin "13") (pinfunction "IN2N_13") (pintype "bidirectional"))
    )
    (net (code "35") (name "IN2P") (class "Default")
      (node (ref "CN5") (pin "5") (pinfunction "C14_5") (pintype "bidirectional"))
      (node (ref "RN4") (pin "8") (pinfunction "P$8_8") (pintype "bidirectional"))
      (node (ref "U1") (pin "14") (pinfunction "IN2P_14") (pintype "bidirectional"))
    )
    (net (code "36") (name "IN3N") (class "Default")
      (node (ref "CN5") (pin "8") (pinfunction "C17_8") (pintype "bidirectional"))
      (node (ref "RN4") (pin "5") (pinfunction "P$5_5") (pintype "bidirectional"))
      (node (ref "U1") (pin "11") (pinfunction "IN3N_11") (pintype "bidirectional"))
    )
    (net (code "37") (name "IN3P") (class "Default")
      (node (ref "CN5") (pin "7") (pinfunction "C16_7") (pintype "bidirectional"))
      (node (ref "RN4") (pin "6") (pinfunction "P$6_6") (pintype "bidirectional"))
      (node (ref "U1") (pin "12") (pinfunction "IN3P_12") (pintype "bidirectional"))
    )
    (net (code "38") (name "IN4N") (class "Default")
      (node (ref "CN4") (pin "6") (pinfunction "C15_6") (pintype "bidirectional"))
      (node (ref "RN3") (pin "7") (pinfunction "P$7_7") (pintype "bidirectional"))
      (node (ref "U1") (pin "9") (pinfunction "IN4N_9") (pintype "bidirectional"))
    )
    (net (code "39") (name "IN4P") (class "Default")
      (node (ref "CN4") (pin "5") (pinfunction "C14_5") (pintype "bidirectional"))
      (node (ref "RN3") (pin "8") (pinfunction "P$8_8") (pintype "bidirectional"))
      (node (ref "U1") (pin "10") (pinfunction "IN4P_10") (pintype "bidirectional"))
    )
    (net (code "40") (name "IN5N") (class "Default")
      (node (ref "CN4") (pin "8") (pinfunction "C17_8") (pintype "bidirectional"))
      (node (ref "RN3") (pin "5") (pinfunction "P$5_5") (pintype "bidirectional"))
      (node (ref "U1") (pin "7") (pinfunction "IN5N_7") (pintype "bidirectional"))
    )
    (net (code "41") (name "IN5P") (class "Default")
      (node (ref "CN4") (pin "7") (pinfunction "C16_7") (pintype "bidirectional"))
      (node (ref "RN3") (pin "6") (pinfunction "P$6_6") (pintype "bidirectional"))
      (node (ref "U1") (pin "8") (pinfunction "IN5P_8") (pintype "bidirectional"))
    )
    (net (code "42") (name "IN6N") (class "Default")
      (node (ref "CN3") (pin "6") (pinfunction "C15_6") (pintype "bidirectional"))
      (node (ref "RN2") (pin "7") (pinfunction "P$7_7") (pintype "bidirectional"))
      (node (ref "U1") (pin "5") (pinfunction "IN6N_5") (pintype "bidirectional"))
    )
    (net (code "43") (name "IN6P") (class "Default")
      (node (ref "CN3") (pin "5") (pinfunction "C14_5") (pintype "bidirectional"))
      (node (ref "RN2") (pin "8") (pinfunction "P$8_8") (pintype "bidirectional"))
      (node (ref "U1") (pin "6") (pinfunction "IN6P_6") (pintype "bidirectional"))
    )
    (net (code "44") (name "IN7N") (class "Default")
      (node (ref "CN3") (pin "8") (pinfunction "C17_8") (pintype "bidirectional"))
      (node (ref "RN2") (pin "5") (pinfunction "P$5_5") (pintype "bidirectional"))
      (node (ref "U1") (pin "3") (pinfunction "IN7N_3") (pintype "bidirectional"))
    )
    (net (code "45") (name "IN7P") (class "Default")
      (node (ref "CN3") (pin "7") (pinfunction "C16_7") (pintype "bidirectional"))
      (node (ref "RN2") (pin "6") (pinfunction "P$6_6") (pintype "bidirectional"))
      (node (ref "U1") (pin "4") (pinfunction "IN7P_4") (pintype "bidirectional"))
    )
    (net (code "46") (name "IN8N") (class "Default")
      (node (ref "CN2") (pin "6") (pinfunction "C15_6") (pintype "bidirectional"))
      (node (ref "RN1") (pin "7") (pinfunction "P$7_7") (pintype "bidirectional"))
      (node (ref "U1") (pin "1") (pinfunction "IN8N_1") (pintype "bidirectional"))
    )
    (net (code "47") (name "IN8P") (class "Default")
      (node (ref "CN2") (pin "5") (pinfunction "C14_5") (pintype "bidirectional"))
      (node (ref "RN1") (pin "8") (pinfunction "P$8_8") (pintype "bidirectional"))
      (node (ref "U1") (pin "2") (pinfunction "IN8P_2") (pintype "bidirectional"))
    )
    (net (code "48") (name "Net-(C22-+)") (class "Default")
      (node (ref "C22") (pin "1") (pinfunction "+_1") (pintype "bidirectional"))
      (node (ref "U1") (pin "28") (pinfunction "VCAP1_28") (pintype "bidirectional"))
    )
    (net (code "49") (name "Net-(C30-Pad1)") (class "Default")
      (node (ref "C30") (pin "1") (pinfunction "1_1") (pintype "passive"))
      (node (ref "R10") (pin "2") (pinfunction "2_2") (pintype "passive"))
      (node (ref "R11") (pin "1") (pinfunction "1_1") (pintype "passive"))
    )
    (net (code "50") (name "Net-(RAW_EDA_SIG-P$1)") (class "Default")
      (node (ref "C31") (pin "1") (pinfunction "1_1") (pintype "passive"))
      (node (ref "R14") (pin "2") (pinfunction "2_2") (pintype "passive"))
      (node (ref "RAW_EDA_SIG") (pin "X") (pinfunction "P$1_X") (pintype "passive"))
      (node (ref "U3") (pin "5") (pinfunction "+INB_5") (pintype "input"))
    )
    (net (code "51") (name "Net-(U1-BIASIN)") (class "Default")
      (node (ref "C9") (pin "1") (pinfunction "1_1") (pintype "passive"))
      (node (ref "R2") (pin "1") (pinfunction "1_1") (pintype "passive"))
      (node (ref "U1") (pin "62") (pinfunction "BIASIN_62") (pintype "bidirectional"))
      (node (ref "U1") (pin "63") (pinfunction "BIASOUT_63") (pintype "bidirectional"))
    )
    (net (code "52") (name "Net-(U1-GPIO1)") (class "Default")
      (node (ref "R6") (pin "2") (pinfunction "2_2") (pintype "passive"))
      (node (ref "U1") (pin "42") (pinfunction "GPIO1_42") (pintype "bidirectional"))
    )
    (net (code "53") (name "Net-(U1-GPIO2)") (class "Default")
      (node (ref "R5") (pin "2") (pinfunction "2_2") (pintype "passive"))
      (node (ref "U1") (pin "44") (pinfunction "GPIO2_44") (pintype "bidirectional"))
    )
    (net (code "54") (name "Net-(U1-GPIO3)") (class "Default")
      (node (ref "R4") (pin "2") (pinfunction "2_2") (pintype "passive"))
      (node (ref "U1") (pin "45") (pinfunction "GPIO3_45") (pintype "bidirectional"))
    )
    (net (code "55") (name "Net-(U1-GPIO4)") (class "Default")
      (node (ref "R3") (pin "2") (pinfunction "2_2") (pintype "passive"))
      (node (ref "U1") (pin "46") (pinfunction "GPIO4_46") (pintype "bidirectional"))
    )
    (net (code "56") (name "Net-(U1-START)") (class "Default")
      (node (ref "R1") (pin "2") (pinfunction "2_2") (pintype "passive"))
      (node (ref "U1") (pin "38") (pinfunction "START_38") (pintype "bidirectional"))
    )
    (net (code "57") (name "Net-(U1-VCAP2)") (class "Default")
      (node (ref "C20") (pin "1") (pinfunction "1_1") (pintype "passive"))
      (node (ref "U1") (pin "30") (pinfunction "VCAP2_30") (pintype "bidirectional"))
    )
    (net (code "58") (name "Net-(U1-VCAP3)") (class "Default")
      (node (ref "C11") (pin "2") (pinfunction "2_2") (pintype "passive"))
      (node (ref "C12") (pin "2") (pinfunction "2_2") (pintype "passive"))
      (node (ref "U1") (pin "55") (pinfunction "VCAP3_55") (pintype "bidirectional"))
    )
    (net (code "59") (name "Net-(U1-VCAP4)") (class "Default")
      (node (ref "C21") (pin "1") (pinfunction "1_1") (pintype "passive"))
      (node (ref "U1") (pin "26") (pinfunction "VCAP4_26") (pintype "bidirectional"))
    )
    (net (code "60") (name "Net-(U1-VREFP)") (class "Default")
      (node (ref "C15") (pin "2") (pinfunction "2_2") (pintype "passive"))
      (node (ref "C23") (pin "1") (pinfunction "1_1") (pintype "passive"))
      (node (ref "U1") (pin "24") (pinfunction "VREFP_24") (pintype "bidirectional"))
    )
    (net (code "61") (name "Net-(U2-+INB)") (class "Default")
      (node (ref "C24") (pin "2") (pinfunction "2_2") (pintype "passive"))
      (node (ref "C25") (pin "1") (pinfunction "1_1") (pintype "passive"))
      (node (ref "C27") (pin "1") (pinfunction "1_1") (pintype "passive"))
      (node (ref "U2") (pin "1") (pinfunction "OUTA_1") (pintype "output"))
      (node (ref "U2") (pin "2") (pinfunction "-INA_2") (pintype "input"))
      (node (ref "U2") (pin "5") (pinfunction "+INB_5") (pintype "input"))
    )
    (net (code "62") (name "Net-(U3-+INA)") (class "Default")
      (node (ref "C28") (pin "1") (pinfunction "1_1") (pintype "passive"))
      (node (ref "R11") (pin "2") (pinfunction "2_2") (pintype "passive"))
      (node (ref "U3") (pin "3") (pinfunction "+INA_3") (pintype "input"))
    )
    (net (code "63") (name "Net-(U3--INA)") (class "Default")
      (node (ref "C30") (pin "2") (pinfunction "2_2") (pintype "passive"))
      (node (ref "R14") (pin "1") (pinfunction "1_1") (pintype "passive"))
      (node (ref "U3") (pin "1") (pinfunction "OUTA_1") (pintype "output"))
      (node (ref "U3") (pin "2") (pinfunction "-INA_2") (pintype "input"))
    )
    (net (code "64") (name "Net-(U3--INB)") (class "Default")
      (node (ref "R15") (pin "1") (pinfunction "1_1") (pintype "passive"))
      (node (ref "U3") (pin "6") (pinfunction "-INB_6") (pintype "input"))
      (node (ref "U3") (pin "7") (pinfunction "OUTB_7") (pintype "output"))
    )
    (net (code "65") (name "Net-(U4-LED_CATHODE)") (class "Default")
      (node (ref "R16") (pin "2") (pinfunction "2_2") (pintype "passive"))
      (node (ref "U4") (pin "1") (pinfunction "LED_CATHODE_1") (pintype "bidirectional"))
    )
    (net (code "66") (name "Net-(U4-PD2_CATHODE)") (class "Default")
      (node (ref "C16") (pin "1") (pinfunction "1_1") (pintype "passive"))
      (node (ref "R17") (pin "1") (pinfunction "1_1") (pintype "passive"))
      (node (ref "U4") (pin "6") (pinfunction "PD2_CATHODE_6") (pintype "bidirectional"))
      (node (ref "U5") (pin "4") (pinfunction "IN-_4") (pintype "input"))
    )
    (net (code "67") (name "Net-(U12-IN-)") (class "Default")
      (node (ref "C10") (pin "1") (pinfunction "1_1") (pintype "passive"))
      (node (ref "R15") (pin "2") (pinfunction "2_2") (pintype "passive"))
      (node (ref "U12") (pin "4") (pinfunction "IN-_4") (pintype "input"))
      (node (ref "U4") (pin "3") (pinfunction "PD1_CATHODE_3") (pintype "bidirectional"))
    )
    (net (code "68") (name "Net-(U12-OUT)") (class "Default")
      (node (ref "C10") (pin "2") (pinfunction "2_2") (pintype "passive"))
      (node (ref "R16") (pin "1") (pinfunction "1_1") (pintype "passive"))
      (node (ref "U12") (pin "1") (pinfunction "OUT_1") (pintype "output"))
    )
    (net (code "69") (name "Net-(U13-VISO)") (class "Default")
      (node (ref "C51") (pin "2") (pinfunction "2_2") (pintype "passive"))
      (node (ref "L1") (pin "1") (pinfunction "1_1") (pintype "bidirectional"))
      (node (ref "U13") (pin "6") (pinfunction "VISO_6") (pintype "bidirectional"))
    )
    (net (code "70") (name "PA02_EDA_SIG") (class "Default")
      (node (ref "C16") (pin "2") (pinfunction "2_2") (pintype "passive"))
      (node (ref "J2") (pin "23") (pinfunction "23_23") (pintype "passive"))
      (node (ref "PA02_EDA_SIG") (pin "X") (pinfunction "P$1_X") (pintype "passive"))
      (node (ref "R17") (pin "2") (pinfunction "2_2") (pintype "passive"))
      (node (ref "U5") (pin "1") (pinfunction "OUT_1") (pintype "output"))
    )
    (net (code "71") (name "PA16_S1_MOSI") (class "Default")
      (node (ref "J2") (pin "1") (pinfunction "1_1") (pintype "passive"))
      (node (ref "U1") (pin "34") (pinfunction "DIN_34") (pintype "bidirectional"))
    )
    (net (code "72") (name "PA17_S1_SCK") (class "Default")
      (node (ref "J2") (pin "5") (pinfunction "5_5") (pintype "passive"))
      (node (ref "U1") (pin "40") (pinfunction "SCLK_40") (pintype "bidirectional"))
    )
    (net (code "73") (name "PA19_S1_MISO") (class "Default")
      (node (ref "J2") (pin "6") (pinfunction "6_6") (pintype "passive"))
      (node (ref "U1") (pin "43") (pinfunction "DOUT_43") (pintype "bidirectional"))
    )
    (net (code "74") (name "PA20_CS") (class "Default")
      (node (ref "J2") (pin "4") (pinfunction "4_4") (pintype "passive"))
      (node (ref "U1") (pin "39") (pinfunction "~{CS}_39") (pintype "bidirectional"))
    )
    (net (code "75") (name "PB10_DRDY") (class "Default")
      (node (ref "J2") (pin "7") (pinfunction "7_7") (pintype "passive"))
      (node (ref "U1") (pin "47") (pinfunction "~{DRDY}_47") (pintype "bidirectional"))
    )
    (net (code "76") (name "S0_I2C_SCL") (class "Default")
      (node (ref "J1") (pin "23") (pinfunction "23_23") (pintype "passive"))
      (node (ref "J2") (pin "9") (pinfunction "9_9") (pintype "passive"))
    )
    (net (code "77") (name "S0_I2C_SDA") (class "Default")
      (node (ref "J1") (pin "24") (pinfunction "24_24") (pintype "passive"))
      (node (ref "J2") (pin "8") (pinfunction "8_8") (pintype "passive"))
    )
    (net (code "78") (name "SRB1") (class "Default")
      (node (ref "J4") (pin "1") (pinfunction "1_1") (pintype "passive"))
      (node (ref "RN5") (pin "3") (pinfunction "P$3_3") (pintype "bidirectional"))
      (node (ref "U10") (pin "2") (pinfunction "IO2_2") (pintype "bidirectional"))
    )
    (net (code "79") (name "SRB2") (class "Default")
      (node (ref "J4") (pin "2") (pinfunction "2_2") (pintype "passive"))
      (node (ref "RN5") (pin "4") (pinfunction "P$4_4") (pintype "bidirectional"))
      (node (ref "U10") (pin "5") (pinfunction "IO4_5") (pintype "bidirectional"))
    )
    (net (code "80") (name "VCC") (class "Default")
      (node (ref "J1") (pin "21") (pinfunction "21_21") (pintype "passive"))
      (node (ref "J1") (pin "22") (pinfunction "22_22") (pintype "passive"))
      (node (ref "J2") (pin "13") (pinfunction "13_13") (pintype "passive"))
      (node (ref "J2") (pin "14") (pinfunction "14_14") (pintype "passive"))
    )
    (net (code "81") (name "_SRB1") (class "Default")
      (node (ref "CN6") (pin "6") (pinfunction "C15_6") (pintype "bidirectional"))
      (node (ref "RN5") (pin "7") (pinfunction "P$7_7") (pintype "bidirectional"))
      (node (ref "U1") (pin "17") (pinfunction "SRB1_17") (pintype "bidirectional"))
    )
    (net (code "82") (name "_SRB2") (class "Default")
      (node (ref "CN6") (pin "5") (pinfunction "C14_5") (pintype "bidirectional"))
      (node (ref "RN5") (pin "8") (pinfunction "P$8_8") (pintype "bidirectional"))
      (node (ref "U1") (pin "18") (pinfunction "SRB2_18") (pintype "bidirectional"))
    )
    (net (code "83") (name "unconnected-(J1-PadMP1)") (class "Default")
      (node (ref "J1") (pin "MP1") (pinfunction "MP1_MP1") (pintype "passive"))
    )
    (net (code "84") (name "unconnected-(J1-PadMP2)") (class "Default")
      (node (ref "J1") (pin "MP2") (pinfunction "MP2_MP2") (pintype "passive"))
    )
    (net (code "85") (name "unconnected-(J2-Pad24)") (class "Default")
      (node (ref "J2") (pin "24") (pinfunction "24_24") (pintype "passive"))
    )
    (net (code "86") (name "unconnected-(J2-PadMP1)") (class "Default")
      (node (ref "J2") (pin "MP1") (pinfunction "MP1_MP1") (pintype "passive"))
    )
    (net (code "87") (name "unconnected-(J2-PadMP2)") (class "Default")
      (node (ref "J2") (pin "MP2") (pinfunction "MP2_MP2") (pintype "passive"))
    )
    (net (code "88") (name "unconnected-(J3-PadMP1)") (class "Default")
      (node (ref "J3") (pin "MP1") (pinfunction "MP1_MP1") (pintype "passive"))
    )
    (net (code "89") (name "unconnected-(J3-PadMP2)") (class "Default")
      (node (ref "J3") (pin "MP2") (pinfunction "MP2_MP2") (pintype "passive"))
    )
    (net (code "90") (name "unconnected-(U1-DAISY_IN-Pad41)") (class "Default")
      (node (ref "U1") (pin "41") (pinfunction "DAISY_IN_41") (pintype "bidirectional"))
    )
    (net (code "91") (name "unconnected-(U1-NC_1-Pad27)") (class "Default")
      (node (ref "U1") (pin "27") (pinfunction "NC_1_27") (pintype "bidirectional"))
    )
    (net (code "92") (name "unconnected-(U1-NC_2-Pad29)") (class "Default")
      (node (ref "U1") (pin "29") (pinfunction "NC_2_29") (pintype "bidirectional"))
    )
    (net (code "93") (name "unconnected-(U1-RESERVED-Pad64)") (class "Default")
      (node (ref "U1") (pin "64") (pinfunction "RESERVED_64") (pintype "bidirectional"))
    )
    (net (code "94") (name "unconnected-(U4-NC_1-Pad7)") (class "Default")
      (node (ref "U4") (pin "7") (pinfunction "NC_1_7") (pintype "bidirectional"))
    )
    (net (code "95") (name "unconnected-(U4-NC_2-Pad8)") (class "Default")
      (node (ref "U4") (pin "8") (pinfunction "NC_2_8") (pintype "bidirectional"))
    )
    (net (code "96") (name "unconnected-(U6-IO1-Pad1)") (class "Default")
      (node (ref "U6") (pin "1") (pinfunction "IO1_1") (pintype "bidirectional"))
    )
    (net (code "97") (name "unconnected-(U6-NC-Pad6)") (class "Default")
      (node (ref "U6") (pin "6") (pinfunction "NC_6") (pintype "no_connect"))
    )
    (net (code "98") (name "unconnected-(U7-NC-Pad6)") (class "Default")
      (node (ref "U7") (pin "6") (pinfunction "NC_6") (pintype "no_connect"))
    )
    (net (code "99") (name "unconnected-(U8-NC-Pad6)") (class "Default")
      (node (ref "U8") (pin "6") (pinfunction "NC_6") (pintype "no_connect"))
    )
    (net (code "100") (name "unconnected-(U9-NC-Pad6)") (class "Default")
      (node (ref "U9") (pin "6") (pinfunction "NC_6") (pintype "no_connect"))
    )
    (net (code "101") (name "unconnected-(U10-NC-Pad6)") (class "Default")
      (node (ref "U10") (pin "6") (pinfunction "NC_6") (pintype "no_connect"))
    )
    (net (code "102") (name "unconnected-(U11-IO4-Pad5)") (class "Default")
      (node (ref "U11") (pin "5") (pinfunction "IO4_5") (pintype "bidirectional"))
    )
    (net (code "103") (name "unconnected-(U11-NC-Pad6)") (class "Default")
      (node (ref "U11") (pin "6") (pinfunction "NC_6") (pintype "no_connect"))
    )
  )
)
